# IR.net
KiCad netlist of a schematic drawn in Altium Designer
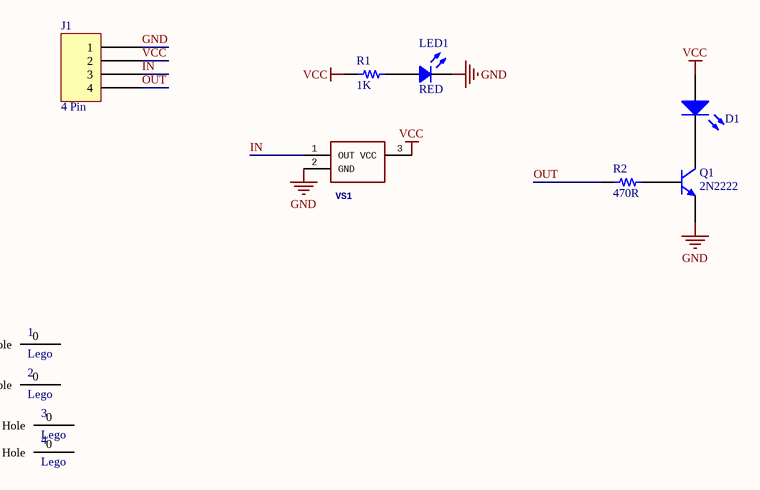
[diagram p0: IR.SchDoc]

(export (version "E")
  (design (tool "Eeschema 10.0.6"))
  (components
    (comp (ref "1") (value "Lego") (footprint "Lego Hole") (libsource (lib "Connectors") (part "Lego")))
    (comp (ref "2") (value "Lego") (footprint "Lego Hole") (libsource (lib "Connectors") (part "Lego")))
    (comp (ref "3") (value "Lego") (footprint "Lego Hole") (libsource (lib "Connectors") (part "Lego")))
    (comp (ref "4") (value "Lego") (footprint "Lego Hole") (libsource (lib "Connectors") (part "Lego")))
    (comp (ref "D1")
      (value "LED 5mm")
      (footprint "LED-1")
      (description "Typical LED")
      (fields (field (name "DESIGNER") "Seyed Mohsen Ghasemian") (field (name "PUBLISHER") "www.picpars.com"))
      (libsource (lib "usefully_Library") (part "LED 5mm"))
    )
    (comp (ref "J1")
      (value "4 Pin")
      (footprint "JST XH B4B-XH-A - RIGHT")
      (libsource (lib "Connectors") (part "4 Pin"))
    )
    (comp (ref "LED1")
      (value "RED")
      (footprint "LED 0805/2012 RED")
      (description "Chip LED")
      (libsource (lib "Cap_Res") (part "LED"))
    )
    (comp (ref "Q1")
      (value "2N2222")
      (footprint "SOT23")
      (description "NPN")
      (fields (field (name "E-MAIL") "picpars@gmail.com"))
      (libsource (lib "Other") (part "2N2222"))
    )
    (comp (ref "R1")
      (value "1K")
      (footprint "RES 1206/3216")
      (description "SMT Resistor")
      (libsource (lib "Cap_Res") (part "Resistor"))
    )
    (comp (ref "R2")
      (value "470R")
      (footprint "RES 1206/3216")
      (description "SMT Resistor")
      (libsource (lib "Cap_Res") (part "Resistor"))
    )
    (comp (ref "VS1")
      (value "~")
      (footprint "VS1838")
      (fields (field (name "RS_PART_NUMBER") "8749069") (field (name "MANUFACTURER_PART_NUMBER") "SS49E-T3"))
      (libsource (lib "Sensors") (part "VS1838"))
    )
  )
  (nets
    (net (code "1") (name "/IN") (class "Default")
      (node (ref "J1") (pin "3") (pinfunction "3_3") (pintype "passive"))
      (node (ref "VS1") (pin "1") (pinfunction "OUT_1") (pintype "passive"))
    )
    (net (code "2") (name "/OUT") (class "Default")
      (node (ref "J1") (pin "4") (pinfunction "4_4") (pintype "passive"))
      (node (ref "R2") (pin "2") (pinfunction "2_2") (pintype "passive"))
    )
    (net (code "3") (name "GND") (class "Default")
      (node (ref "J1") (pin "1") (pinfunction "1_1") (pintype "passive"))
      (node (ref "LED1") (pin "2") (pinfunction "2_2") (pintype "passive"))
      (node (ref "Q1") (pin "E") (pinfunction "E_E") (pintype "passive"))
      (node (ref "VS1") (pin "2") (pinfunction "GND_2") (pintype "passive"))
    )
    (net (code "4") (name "Net-(D1-K)") (class "Default")
      (node (ref "D1") (pin "2") (pinfunction "K_2") (pintype "passive"))
      (node (ref "Q1") (pin "C") (pinfunction "C_C") (pintype "passive"))
    )
    (net (code "5") (name "Net-(LED1-Pad1)") (class "Default")
      (node (ref "LED1") (pin "1") (pinfunction "1_1") (pintype "passive"))
      (node (ref "R1") (pin "1") (pinfunction "1_1") (pintype "passive"))
    )
    (net (code "6") (name "Net-(Q1-PadB)") (class "Default")
      (node (ref "Q1") (pin "B") (pinfunction "B_B") (pintype "passive"))
      (node (ref "R2") (pin "1") (pinfunction "1_1") (pintype "passive"))
    )
    (net (code "7") (name "VCC") (class "Default")
      (node (ref "D1") (pin "1") (pinfunction "A_1") (pintype "passive"))
      (node (ref "J1") (pin "2") (pinfunction "2_2") (pintype "passive"))
      (node (ref "R1") (pin "2") (pinfunction "2_2") (pintype "passive"))
      (node (ref "VS1") (pin "3") (pinfunction "VCC_3") (pintype "passive"))
    )
    (net (code "8") (name "unconnected-(1-Lego_Hole-Pad0)") (class "Default")
      (node (ref "1") (pin "0") (pinfunction "Lego_Hole_0") (pintype "passive"))
    )
    (net (code "9") (name "unconnected-(2-Lego_Hole-Pad0)") (class "Default")
      (node (ref "2") (pin "0") (pinfunction "Lego_Hole_0") (pintype "passive"))
    )
    (net (code "10") (name "unconnected-(3-Lego_Hole-Pad0)") (class "Default")
      (node (ref "3") (pin "0") (pinfunction "Lego_Hole_0") (pintype "passive"))
    )
    (net (code "11") (name "unconnected-(4-Lego_Hole-Pad0)") (class "Default")
      (node (ref "4") (pin "0") (pinfunction "Lego_Hole_0") (pintype "passive"))
    )
  )
)
